# Flow_sensor.net
KiCad netlist of a schematic drawn in Altium Designer
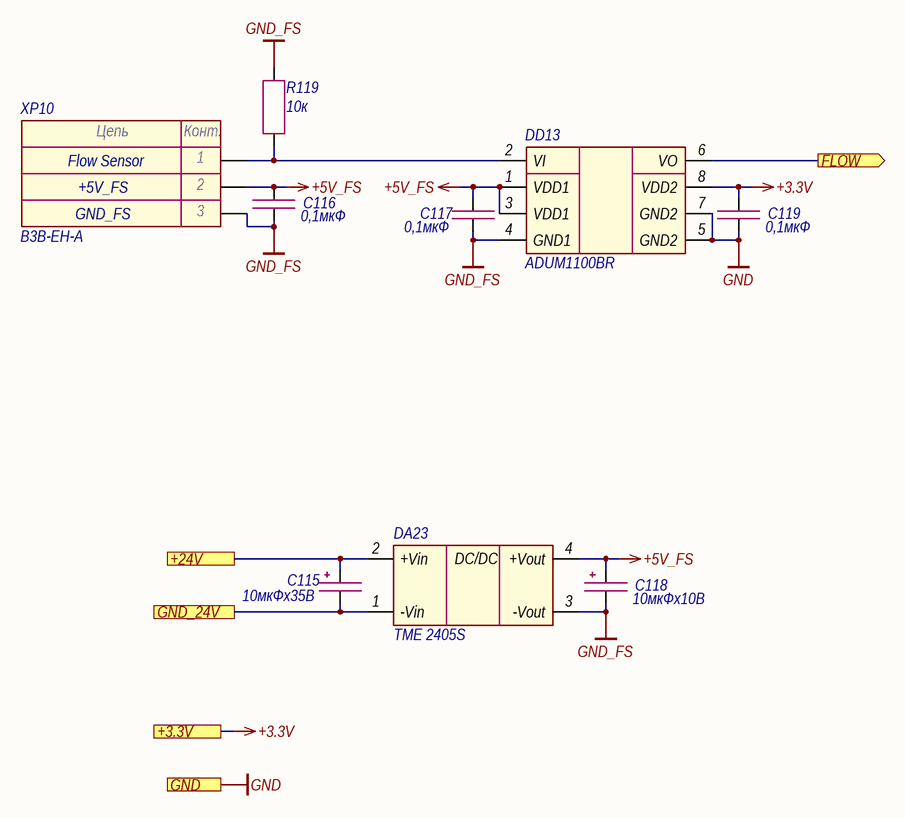
[diagram p0: Flow_sensor.SchDoc]

(export (version "E")
  (design (tool "Eeschema 10.0.6"))
  (components
    (comp (ref "C115")
      (value "10мкФх35B")
      (footprint "Pcb_library:CAP_C")
      (libsource (lib "Schem_library") (part "Capacitor_Polar"))
    )
    (comp (ref "C116")
      (value "0,1мкФ")
      (footprint "Pcb_library:CAP_0603")
      (fields (field (name "MANUFACTURER") "Murata"))
      (libsource (lib "Schem_library") (part "Capacitor"))
    )
    (comp (ref "C117")
      (value "0,1мкФ")
      (footprint "Pcb_library:CAP_0603")
      (fields (field (name "MANUFACTURER") "Murata"))
      (libsource (lib "Schem_library") (part "Capacitor"))
    )
    (comp (ref "C118")
      (value "10мкФх10B")
      (footprint "Pcb_library:CAP_A")
      (libsource (lib "Schem_library") (part "Capacitor_Polar"))
    )
    (comp (ref "C119")
      (value "0,1мкФ")
      (footprint "Pcb_library:CAP_0603")
      (fields (field (name "MANUFACTURER") "Murata"))
      (libsource (lib "Schem_library") (part "Capacitor"))
    )
    (comp (ref "DA23")
      (value "TME 2405S")
      (footprint "Pcb_library:TME (SIP-4)")
      (fields (field (name "MANUFACTURER") "Traco Power"))
      (libsource (lib "Schem_library") (part "TME"))
    )
    (comp (ref "DD13")
      (value "ADUM1100BR")
      (footprint "Pcb_library:SOIC-8")
      (fields (field (name "MANUFACTURER") "Analog Devices"))
      (libsource (lib "Schem_library") (part "ADUM1100"))
    )
    (comp (ref "R119")
      (value "10к")
      (footprint "Pcb_library:RES_0603")
      (fields (field (name "MANUFACTURER") "Yageo"))
      (libsource (lib "Schem_library") (part "Resistor"))
    )
    (comp (ref "XP10")
      (value "B3B-EH-A")
      (footprint "B3B-EH-A")
      (fields (field (name "MANUFACTURER") "JST"))
      (libsource (lib "Schem_library") (part "Connector-3"))
    )
  )
  (nets
    (net (code "1") (name "+3.3V") (class "Default")
      (node (ref "C119") (pin "1") (pinfunction "1_1") (pintype "passive"))
      (node (ref "DD13") (pin "8") (pinfunction "VDD2_8") (pintype "passive"))
    )
    (net (code "2") (name "+5V_FS") (class "Default")
      (node (ref "C116") (pin "1") (pinfunction "1_1") (pintype "passive"))
      (node (ref "C117") (pin "1") (pinfunction "1_1") (pintype "passive"))
      (node (ref "C118") (pin "1") (pinfunction "1_1") (pintype "passive"))
      (node (ref "DA23") (pin "4") (pinfunction "+Vout_4") (pintype "passive"))
      (node (ref "DD13") (pin "1") (pinfunction "VDD1_1") (pintype "passive"))
      (node (ref "DD13") (pin "3") (pinfunction "VDD1_3") (pintype "passive"))
      (node (ref "XP10") (pin "2") (pintype "passive"))
    )
    (net (code "3") (name "/+24V") (class "Default")
      (node (ref "C115") (pin "1") (pinfunction "1_1") (pintype "passive"))
      (node (ref "DA23") (pin "2") (pinfunction "+Vin_2") (pintype "passive"))
    )
    (net (code "4") (name "/FLOW") (class "Default")
      (node (ref "DD13") (pin "6") (pinfunction "VO_6") (pintype "passive"))
    )
    (net (code "5") (name "/GND_24V") (class "Default")
      (node (ref "C115") (pin "2") (pinfunction "2_2") (pintype "passive"))
      (node (ref "DA23") (pin "1") (pinfunction "-Vin_1") (pintype "passive"))
    )
    (net (code "6") (name "GND") (class "Default")
      (node (ref "C119") (pin "2") (pinfunction "2_2") (pintype "passive"))
      (node (ref "DD13") (pin "5") (pinfunction "GND2_5") (pintype "passive"))
      (node (ref "DD13") (pin "7") (pinfunction "GND2_7") (pintype "passive"))
    )
    (net (code "7") (name "GND_FS") (class "Default")
      (node (ref "C116") (pin "2") (pinfunction "2_2") (pintype "passive"))
      (node (ref "C117") (pin "2") (pinfunction "2_2") (pintype "passive"))
      (node (ref "C118") (pin "2") (pinfunction "2_2") (pintype "passive"))
      (node (ref "DA23") (pin "3") (pinfunction "-Vout_3") (pintype "passive"))
      (node (ref "DD13") (pin "4") (pinfunction "GND1_4") (pintype "passive"))
      (node (ref "R119") (pin "2") (pinfunction "2_2") (pintype "passive"))
      (node (ref "XP10") (pin "3") (pintype "passive"))
    )
    (net (code "8") (name "Net-(DD13-VI)") (class "Default")
      (node (ref "DD13") (pin "2") (pinfunction "VI_2") (pintype "passive"))
      (node (ref "R119") (pin "1") (pinfunction "1_1") (pintype "passive"))
      (node (ref "XP10") (pin "1") (pintype "passive"))
    )
  )
)
